# dynext_v0_2.net
KiCad netlist of a schematic drawn in EAGLE
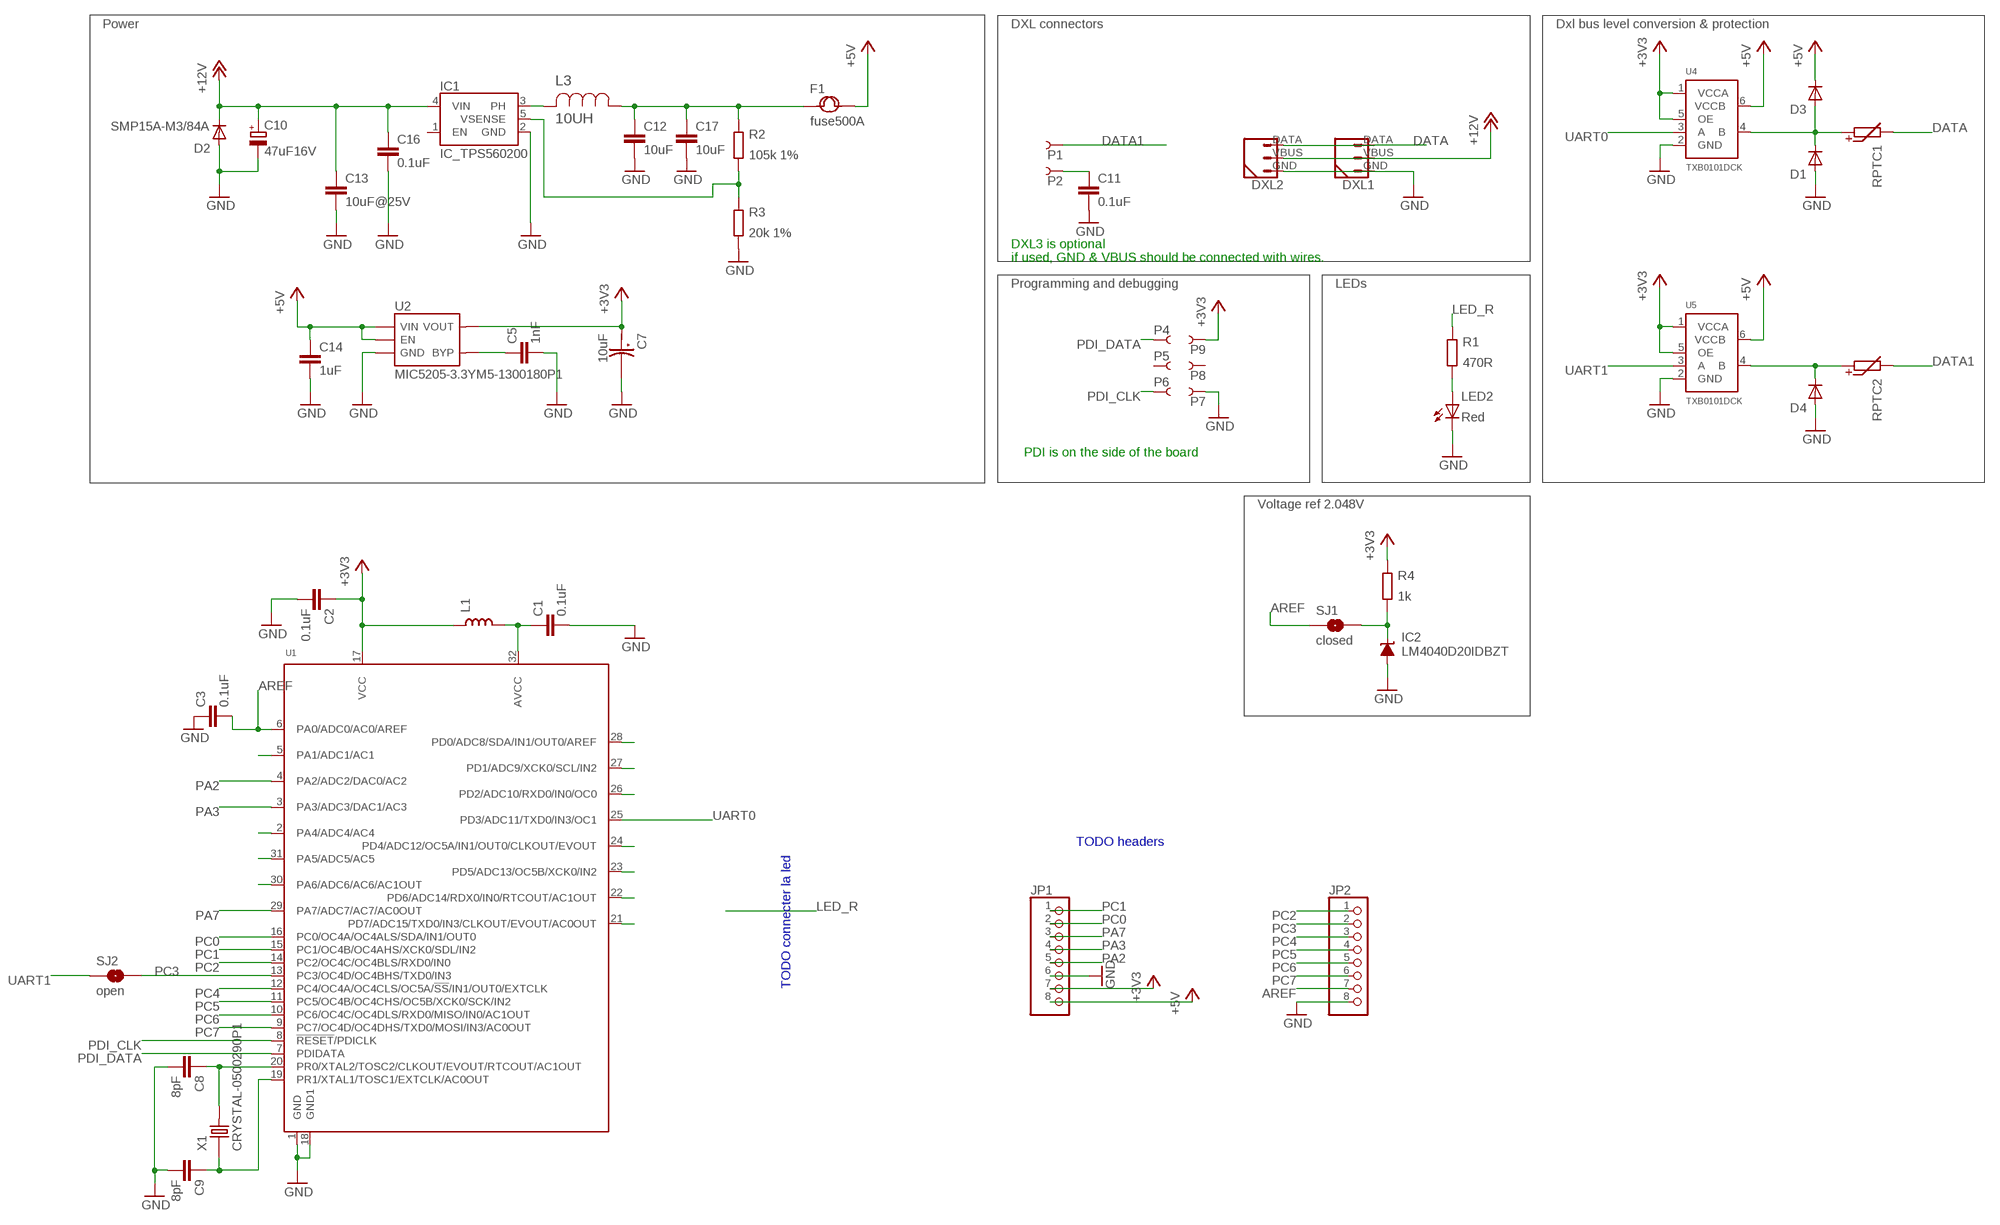
[diagram p0: schematic, sheet 1]

(export (version "E")
  (design (tool "Eeschema 10.0.6"))
  (components
    (comp (ref "C1")
      (value "0.1uF")
      (footprint "eagle-import:0402_N")
      (libsource (lib "eagle-import") (part "C0402"))
    )
    (comp (ref "C2")
      (value "0.1uF")
      (footprint "eagle-import:0402_N")
      (libsource (lib "eagle-import") (part "C0402"))
    )
    (comp (ref "C3")
      (value "0.1uF")
      (footprint "eagle-import:0402_N")
      (libsource (lib "eagle-import") (part "C0402"))
    )
    (comp (ref "C5")
      (value "1nF")
      (footprint "eagle-import:0402_N")
      (libsource (lib "eagle-import") (part "C0402"))
    )
    (comp (ref "C7")
      (value "10uF")
      (footprint "eagle-import:AVX-A")
      (libsource (lib "eagle-import") (part "C-POLAR-A"))
    )
    (comp (ref "C8")
      (value "8pF")
      (footprint "eagle-import:0402_N")
      (libsource (lib "eagle-import") (part "C0402"))
    )
    (comp (ref "C9")
      (value "8pF")
      (footprint "eagle-import:0402_N")
      (libsource (lib "eagle-import") (part "C0402"))
    )
    (comp (ref "C10")
      (value "47uF16V")
      (footprint "eagle-import:UD-5X5,8_NICHICON")
      (libsource (lib "eagle-import") (part "CPOL-EUUD-5X5,8"))
    )
    (comp (ref "C11")
      (value "0.1uF")
      (footprint "eagle-import:0402_N")
      (libsource (lib "eagle-import") (part "C0402"))
    )
    (comp (ref "C12")
      (value "10uF")
      (footprint "eagle-import:0805_N")
      (libsource (lib "eagle-import") (part "C0805"))
    )
    (comp (ref "C13")
      (value "10uF@25V")
      (footprint "eagle-import:0805_N")
      (libsource (lib "eagle-import") (part "C0805"))
    )
    (comp (ref "C14")
      (value "1uF")
      (footprint "eagle-import:0402_N")
      (libsource (lib "eagle-import") (part "C0402"))
    )
    (comp (ref "C16")
      (value "0.1uF")
      (footprint "eagle-import:0402_N")
      (libsource (lib "eagle-import") (part "C0402"))
    )
    (comp (ref "C17")
      (value "10uF")
      (footprint "eagle-import:0805_N")
      (libsource (lib "eagle-import") (part "C0805"))
    )
    (comp (ref "D1")
      (value "DIODE-SOD523")
      (footprint "eagle-import:SOD-523_N")
      (libsource (lib "eagle-import") (part "DIODE-SOD523"))
    )
    (comp (ref "D2")
      (value "SMP15A-M3/84A")
      (footprint "eagle-import:DO-220AA")
      (libsource (lib "eagle-import") (part "DIODE-SMP"))
    )
    (comp (ref "D3")
      (value "DIODE-SOD523")
      (footprint "eagle-import:SOD-523_N")
      (libsource (lib "eagle-import") (part "DIODE-SOD523"))
    )
    (comp (ref "D4")
      (value "DIODE-SOD523")
      (footprint "eagle-import:SOD-523_N")
      (libsource (lib "eagle-import") (part "DIODE-SOD523"))
    )
    (comp (ref "DXL1")
      (value "DYNAMIXEL_3POS-T")
      (footprint "eagle-import:DYNAMIXEL_3POS_TOP")
      (libsource (lib "eagle-import") (part "DYNAMIXEL_3POS-T"))
    )
    (comp (ref "DXL2")
      (value "DYNAMIXEL_3POS-T")
      (footprint "eagle-import:DYNAMIXEL_3POS_TOP")
      (libsource (lib "eagle-import") (part "DYNAMIXEL_3POS-T"))
    )
    (comp (ref "F1")
      (value "fuse500A")
      (footprint "eagle-import:F1206")
      (libsource (lib "eagle-import") (part "FUSE-1206"))
    )
    (comp (ref "IC1")
      (value "IC_TPS560200")
      (footprint "eagle-import:SOT-23-5_N")
      (libsource (lib "eagle-import") (part "IC_TPS560200"))
    )
    (comp (ref "IC2")
      (value "LM4040D20IDBZT")
      (footprint "eagle-import:DBZ_R-PDSO-G3")
      (fields (field (name "MPN") "LM4041A12IDBZR"))
      (libsource (lib "eagle-import") (part "LM4041DBZA12"))
    )
    (comp (ref "JP1")
      (value "PINHD-1X8R")
      (footprint "eagle-import:1X08_ROUND")
      (libsource (lib "eagle-import") (part "PINHD-1X8R"))
    )
    (comp (ref "JP2")
      (value "PINHD-1X8R")
      (footprint "eagle-import:1X08_ROUND")
      (libsource (lib "eagle-import") (part "PINHD-1X8R"))
    )
    (comp (ref "L1")
      (value "L0603")
      (footprint "eagle-import:0603_N")
      (libsource (lib "eagle-import") (part "L0603"))
    )
    (comp (ref "L3")
      (value "10UH")
      (footprint "eagle-import:IND_ELL4XG")
      (fields (field (name "MPN") "ELL4LG100MA"))
      (libsource (lib "eagle-import") (part "ELL-4XG4LG100MA"))
    )
    (comp (ref "LED2")
      (value "Red")
      (footprint "eagle-import:D_0603_N")
      (libsource (lib "eagle-import") (part "LED0603"))
    )
    (comp (ref "P1")
      (value "PIN_SMD_2X2.5")
      (footprint "eagle-import:PIN_SMD_2X2.5")
      (libsource (lib "eagle-import") (part "PIN_SMD_2X2.5"))
    )
    (comp (ref "P2")
      (value "PIN_SMD_2X2.5")
      (footprint "eagle-import:PIN_SMD_2X2.5")
      (libsource (lib "eagle-import") (part "PIN_SMD_2X2.5"))
    )
    (comp (ref "P4")
      (value "PIN_SMD_2X2.5")
      (footprint "eagle-import:PIN_SMD_2X2.5")
      (libsource (lib "eagle-import") (part "PIN_SMD_2X2.5"))
    )
    (comp (ref "P5")
      (value "PIN_SMD_1X1")
      (footprint "eagle-import:PIN_SMD_1X1")
      (libsource (lib "eagle-import") (part "PIN_SMD_1X1"))
    )
    (comp (ref "P6")
      (value "PIN_SMD_2X2.5")
      (footprint "eagle-import:PIN_SMD_2X2.5")
      (libsource (lib "eagle-import") (part "PIN_SMD_2X2.5"))
    )
    (comp (ref "P7")
      (value "PIN_SMD_2X2.5")
      (footprint "eagle-import:PIN_SMD_2X2.5")
      (libsource (lib "eagle-import") (part "PIN_SMD_2X2.5"))
    )
    (comp (ref "P8")
      (value "PIN_SMD_1X1")
      (footprint "eagle-import:PIN_SMD_1X1")
      (libsource (lib "eagle-import") (part "PIN_SMD_1X1"))
    )
    (comp (ref "P9")
      (value "PIN_SMD_2X2.5")
      (footprint "eagle-import:PIN_SMD_2X2.5")
      (libsource (lib "eagle-import") (part "PIN_SMD_2X2.5"))
    )
    (comp (ref "R1")
      (value "470R")
      (footprint "eagle-import:0402_N")
      (libsource (lib "eagle-import") (part "R0402"))
    )
    (comp (ref "R2")
      (value "105k 1%")
      (footprint "eagle-import:0402_N")
      (libsource (lib "eagle-import") (part "R0402"))
    )
    (comp (ref "R3")
      (value "20k 1%")
      (footprint "eagle-import:0402_N")
      (libsource (lib "eagle-import") (part "R0402"))
    )
    (comp (ref "R4")
      (value "1k")
      (footprint "eagle-import:0402_N")
      (libsource (lib "eagle-import") (part "R0402"))
    )
    (comp (ref "RPTC1")
      (value "R-PTC0603")
      (footprint "eagle-import:0603_N")
      (libsource (lib "eagle-import") (part "R-PTC0603"))
    )
    (comp (ref "RPTC2")
      (value "R-PTC0603")
      (footprint "eagle-import:0603_N")
      (libsource (lib "eagle-import") (part "R-PTC0603"))
    )
    (comp (ref "SJ1")
      (value "closed")
      (footprint "eagle-import:SJ_2S-TRACE2")
      (libsource (lib "eagle-import") (part "SOLDERJUMPER2_TRACE2"))
    )
    (comp (ref "SJ2")
      (value "open")
      (footprint "eagle-import:SJ_2S-NO")
      (libsource (lib "eagle-import") (part "SOLDERJUMPER2NO"))
    )
    (comp (ref "U1")
      (value "ATXMEGAE5-MU_MOD")
      (footprint "eagle-import:QFN-32_50P_L_MOD")
      (libsource (lib "eagle-import") (part "ATXMEGAE5-MU_MOD"))
    )
    (comp (ref "U2")
      (value "MIC5205-3.3YM5-1300180P1")
      (footprint "eagle-import:SOT23-5")
      (libsource (lib "eagle-import") (part "MIC5205-3.3YM5-1300180P1"))
    )
    (comp (ref "U4")
      (value "TXB0101DCK")
      (footprint "eagle-import:SC70-6")
      (libsource (lib "eagle-import") (part "TXB0101DCK"))
    )
    (comp (ref "U5")
      (value "TXB0101DCK")
      (footprint "eagle-import:SC70-6")
      (libsource (lib "eagle-import") (part "TXB0101DCK"))
    )
    (comp (ref "X1")
      (value "CRYSTAL-0500290P1")
      (footprint "eagle-import:2P-SMD-5.0X3.2")
      (libsource (lib "eagle-import") (part "CRYSTAL-0500290P1"))
    )
  )
  (nets
    (net (code "1") (name "+3V3") (class "Default")
      (node (ref "C2") (pin "1") (pinfunction "1_1") (pintype "passive"))
      (node (ref "C7") (pin "+") (pinfunction "1_+") (pintype "bidirectional"))
      (node (ref "JP1") (pin "7") (pinfunction "7_7") (pintype "passive"))
      (node (ref "L1") (pin "1") (pinfunction "1_1") (pintype "passive"))
      (node (ref "P9") (pin "PIN") (pinfunction "1_PIN") (pintype "bidirectional"))
      (node (ref "R4") (pin "2") (pinfunction "2_2") (pintype "passive"))
      (node (ref "U1") (pin "17") (pinfunction "VCC_17") (pintype "bidirectional"))
      (node (ref "U2") (pin "5") (pinfunction "VOUT_5") (pintype "bidirectional"))
      (node (ref "U4") (pin "1") (pinfunction "VCCA_1") (pintype "bidirectional"))
      (node (ref "U4") (pin "5") (pinfunction "OE_5") (pintype "bidirectional"))
      (node (ref "U5") (pin "1") (pinfunction "VCCA_1") (pintype "bidirectional"))
      (node (ref "U5") (pin "5") (pinfunction "OE_5") (pintype "bidirectional"))
    )
    (net (code "2") (name "+5V") (class "Default")
      (node (ref "C14") (pin "1") (pinfunction "1_1") (pintype "passive"))
      (node (ref "D3") (pin "C") (pinfunction "C_C") (pintype "passive"))
      (node (ref "F1") (pin "2") (pinfunction "2_2") (pintype "bidirectional"))
      (node (ref "JP1") (pin "8") (pinfunction "8_8") (pintype "passive"))
      (node (ref "U2") (pin "1") (pinfunction "VIN_1") (pintype "bidirectional"))
      (node (ref "U2") (pin "3") (pinfunction "EN_3") (pintype "bidirectional"))
      (node (ref "U4") (pin "6") (pinfunction "VCCB_6") (pintype "bidirectional"))
      (node (ref "U5") (pin "6") (pinfunction "VCCB_6") (pintype "bidirectional"))
    )
    (net (code "3") (name "+12V") (class "Default")
      (node (ref "C10") (pin "+") (pinfunction "+_+") (pintype "passive"))
      (node (ref "C13") (pin "1") (pinfunction "1_1") (pintype "passive"))
      (node (ref "C16") (pin "1") (pinfunction "1_1") (pintype "passive"))
      (node (ref "D2") (pin "C") (pinfunction "C_C") (pintype "passive"))
      (node (ref "DXL1") (pin "VBUS") (pinfunction "2_VBUS") (pintype "bidirectional"))
      (node (ref "DXL2") (pin "VBUS") (pinfunction "2_VBUS") (pintype "bidirectional"))
      (node (ref "IC1") (pin "4") (pinfunction "VIN_4") (pintype "bidirectional"))
    )
    (net (code "4") (name "/AREF") (class "Default")
      (node (ref "C3") (pin "2") (pinfunction "2_2") (pintype "passive"))
      (node (ref "JP2") (pin "7") (pinfunction "7_7") (pintype "passive"))
      (node (ref "SJ1") (pin "1") (pinfunction "1_1") (pintype "passive"))
      (node (ref "U1") (pin "6") (pinfunction "PA0/ADC0/AC0/AREF_6") (pintype "bidirectional"))
    )
    (net (code "5") (name "/DATA") (class "Default")
      (node (ref "DXL1") (pin "DATA") (pinfunction "3_DATA") (pintype "bidirectional"))
      (node (ref "DXL2") (pin "DATA") (pinfunction "3_DATA") (pintype "bidirectional"))
      (node (ref "RPTC1") (pin "2") (pinfunction "2_2") (pintype "passive"))
    )
    (net (code "6") (name "/DATA1") (class "Default")
      (node (ref "P1") (pin "PIN") (pinfunction "1_PIN") (pintype "bidirectional"))
      (node (ref "RPTC2") (pin "2") (pinfunction "2_2") (pintype "passive"))
    )
    (net (code "7") (name "/LED_R") (class "Default")
      (node (ref "R1") (pin "2") (pinfunction "2_2") (pintype "passive"))
    )
    (net (code "8") (name "/PA2") (class "Default")
      (node (ref "JP1") (pin "5") (pinfunction "5_5") (pintype "passive"))
      (node (ref "U1") (pin "4") (pinfunction "PA2/ADC2/DAC0/AC2_4") (pintype "bidirectional"))
    )
    (net (code "9") (name "/PA3") (class "Default")
      (node (ref "JP1") (pin "4") (pinfunction "4_4") (pintype "passive"))
      (node (ref "U1") (pin "3") (pinfunction "PA3/ADC3/DAC1/AC3_3") (pintype "bidirectional"))
    )
    (net (code "10") (name "/PA7") (class "Default")
      (node (ref "JP1") (pin "3") (pinfunction "3_3") (pintype "passive"))
      (node (ref "U1") (pin "29") (pinfunction "PA7/ADC7/AC7/AC0OUT_29") (pintype "bidirectional"))
    )
    (net (code "11") (name "/PC0") (class "Default")
      (node (ref "JP1") (pin "2") (pinfunction "2_2") (pintype "passive"))
      (node (ref "U1") (pin "16") (pinfunction "PC0/OC4A/OC4ALS/SDA/IN1/OUT0_16") (pintype "bidirectional"))
    )
    (net (code "12") (name "/PC1") (class "Default")
      (node (ref "JP1") (pin "1") (pinfunction "1_1") (pintype "passive"))
      (node (ref "U1") (pin "15") (pinfunction "PC1/OC4B/OC4AHS/XCK0/SDL/IN2_15") (pintype "bidirectional"))
    )
    (net (code "13") (name "/PC2") (class "Default")
      (node (ref "JP2") (pin "1") (pinfunction "1_1") (pintype "passive"))
      (node (ref "U1") (pin "14") (pinfunction "PC2/OC4C/OC4BLS/RXD0/IN0_14") (pintype "bidirectional"))
    )
    (net (code "14") (name "/PC3") (class "Default")
      (node (ref "JP2") (pin "2") (pinfunction "2_2") (pintype "passive"))
      (node (ref "SJ2") (pin "2") (pinfunction "2_2") (pintype "passive"))
      (node (ref "U1") (pin "13") (pinfunction "PC3/OC4D/OC4BHS/TXD0/IN3_13") (pintype "bidirectional"))
    )
    (net (code "15") (name "/PC4") (class "Default")
      (node (ref "JP2") (pin "3") (pinfunction "3_3") (pintype "passive"))
      (node (ref "U1") (pin "12") (pinfunction "PC4/OC4A/OC4CLS/OC5A/~{SS}/IN1/OUT0/EXTCLK_12") (pintype "bidirectional"))
    )
    (net (code "16") (name "/PC5") (class "Default")
      (node (ref "JP2") (pin "4") (pinfunction "4_4") (pintype "passive"))
      (node (ref "U1") (pin "11") (pinfunction "PC5/OC4B/OC4CHS/OC5B/XCK0/SCK/IN2_11") (pintype "bidirectional"))
    )
    (net (code "17") (name "/PC6") (class "Default")
      (node (ref "JP2") (pin "5") (pinfunction "5_5") (pintype "passive"))
      (node (ref "U1") (pin "10") (pinfunction "PC6/OC4C/OC4DLS/RXD0/MISO/IN0/AC1OUT_10") (pintype "bidirectional"))
    )
    (net (code "18") (name "/PC7") (class "Default")
      (node (ref "JP2") (pin "6") (pinfunction "6_6") (pintype "passive"))
      (node (ref "U1") (pin "9") (pinfunction "PC7/OC4D/OC4DHS/TXD0/MOSI/IN3/AC0OUT_9") (pintype "bidirectional"))
    )
    (net (code "19") (name "/PDI_CLK") (class "Default")
      (node (ref "P6") (pin "PIN") (pinfunction "1_PIN") (pintype "bidirectional"))
      (node (ref "U1") (pin "8") (pinfunction "~{RESET}/PDICLK_8") (pintype "bidirectional"))
    )
    (net (code "20") (name "/PDI_DATA") (class "Default")
      (node (ref "P4") (pin "PIN") (pinfunction "1_PIN") (pintype "bidirectional"))
      (node (ref "U1") (pin "7") (pinfunction "PDIDATA_7") (pintype "bidirectional"))
    )
    (net (code "21") (name "/UART0") (class "Default")
      (node (ref "U1") (pin "25") (pinfunction "PD3/ADC11/TXD0/IN3/OC1_25") (pintype "bidirectional"))
      (node (ref "U4") (pin "3") (pinfunction "A_3") (pintype "bidirectional"))
    )
    (net (code "22") (name "/UART1") (class "Default")
      (node (ref "SJ2") (pin "1") (pinfunction "1_1") (pintype "passive"))
      (node (ref "U5") (pin "3") (pinfunction "A_3") (pintype "bidirectional"))
    )
    (net (code "23") (name "GND") (class "Default")
      (node (ref "C1") (pin "2") (pinfunction "2_2") (pintype "passive"))
      (node (ref "C10") (pin "-") (pinfunction "-_-") (pintype "passive"))
      (node (ref "C11") (pin "2") (pinfunction "2_2") (pintype "passive"))
      (node (ref "C12") (pin "2") (pinfunction "2_2") (pintype "passive"))
      (node (ref "C13") (pin "2") (pinfunction "2_2") (pintype "passive"))
      (node (ref "C14") (pin "2") (pinfunction "2_2") (pintype "passive"))
      (node (ref "C16") (pin "2") (pinfunction "2_2") (pintype "passive"))
      (node (ref "C17") (pin "2") (pinfunction "2_2") (pintype "passive"))
      (node (ref "C2") (pin "2") (pinfunction "2_2") (pintype "passive"))
      (node (ref "C3") (pin "1") (pinfunction "1_1") (pintype "passive"))
      (node (ref "C5") (pin "2") (pinfunction "2_2") (pintype "passive"))
      (node (ref "C7") (pin "-") (pinfunction "2_-") (pintype "bidirectional"))
      (node (ref "C8") (pin "2") (pinfunction "2_2") (pintype "passive"))
      (node (ref "C9") (pin "2") (pinfunction "2_2") (pintype "passive"))
      (node (ref "D1") (pin "A") (pinfunction "A_A") (pintype "passive"))
      (node (ref "D2") (pin "A") (pinfunction "A_A") (pintype "passive"))
      (node (ref "D4") (pin "A") (pinfunction "A_A") (pintype "passive"))
      (node (ref "DXL1") (pin "GND") (pinfunction "1_GND") (pintype "bidirectional"))
      (node (ref "DXL2") (pin "GND") (pinfunction "1_GND") (pintype "bidirectional"))
      (node (ref "IC1") (pin "2") (pinfunction "GND_2") (pintype "input"))
      (node (ref "IC2") (pin "2") (pinfunction "A_2") (pintype "passive"))
      (node (ref "JP1") (pin "6") (pinfunction "6_6") (pintype "passive"))
      (node (ref "JP2") (pin "8") (pinfunction "8_8") (pintype "passive"))
      (node (ref "LED2") (pin "C") (pinfunction "C_C") (pintype "passive"))
      (node (ref "P7") (pin "PIN") (pinfunction "1_PIN") (pintype "bidirectional"))
      (node (ref "R3") (pin "1") (pinfunction "1_1") (pintype "passive"))
      (node (ref "U1") (pin "1") (pinfunction "GND_1") (pintype "bidirectional"))
      (node (ref "U1") (pin "18") (pinfunction "GND1_18") (pintype "bidirectional"))
      (node (ref "U2") (pin "2") (pinfunction "GND_2") (pintype "bidirectional"))
      (node (ref "U4") (pin "2") (pinfunction "GND_2") (pintype "bidirectional"))
      (node (ref "U5") (pin "2") (pinfunction "GND_2") (pintype "bidirectional"))
    )
    (net (code "24") (name "Net-(C12-Pad1)") (class "Default")
      (node (ref "C12") (pin "1") (pinfunction "1_1") (pintype "passive"))
      (node (ref "C17") (pin "1") (pinfunction "1_1") (pintype "passive"))
      (node (ref "F1") (pin "1") (pinfunction "1_1") (pintype "bidirectional"))
      (node (ref "L3") (pin "1") (pinfunction "1_1") (pintype "passive"))
      (node (ref "R2") (pin "2") (pinfunction "2_2") (pintype "passive"))
    )
    (net (code "25") (name "Net-(IC1-PH)") (class "Default")
      (node (ref "IC1") (pin "3") (pinfunction "PH_3") (pintype "bidirectional"))
      (node (ref "L3") (pin "2") (pinfunction "2_2") (pintype "passive"))
    )
    (net (code "26") (name "Net-(IC1-VSENSE)") (class "Default")
      (node (ref "IC1") (pin "5") (pinfunction "VSENSE_5") (pintype "bidirectional"))
      (node (ref "R2") (pin "1") (pinfunction "1_1") (pintype "passive"))
      (node (ref "R3") (pin "2") (pinfunction "2_2") (pintype "passive"))
    )
    (net (code "27") (name "Net-(IC2-C)") (class "Default")
      (node (ref "IC2") (pin "1") (pinfunction "C_1") (pintype "passive"))
      (node (ref "R4") (pin "1") (pinfunction "1_1") (pintype "passive"))
      (node (ref "SJ1") (pin "2") (pinfunction "2_2") (pintype "passive"))
    )
    (net (code "28") (name "Net-(LED2-PadA)") (class "Default")
      (node (ref "LED2") (pin "A") (pinfunction "A_A") (pintype "passive"))
      (node (ref "R1") (pin "1") (pinfunction "1_1") (pintype "passive"))
    )
    (net (code "29") (name "Net-(P2-1)") (class "Default")
      (node (ref "C11") (pin "1") (pinfunction "1_1") (pintype "passive"))
      (node (ref "P2") (pin "PIN") (pinfunction "1_PIN") (pintype "bidirectional"))
    )
    (net (code "30") (name "Net-(U1-AVCC)") (class "Default")
      (node (ref "C1") (pin "1") (pinfunction "1_1") (pintype "passive"))
      (node (ref "L1") (pin "2") (pinfunction "2_2") (pintype "passive"))
      (node (ref "U1") (pin "32") (pinfunction "AVCC_32") (pintype "bidirectional"))
    )
    (net (code "31") (name "Net-(U1-PR0{slash}XTAL2{slash}TOSC2{slash}CLKOUT{slash}EVOUT{slash}RTCOUT{slash}AC1OUT)") (class "Default")
      (node (ref "C8") (pin "1") (pinfunction "1_1") (pintype "passive"))
      (node (ref "U1") (pin "20") (pinfunction "PR0/XTAL2/TOSC2/CLKOUT/EVOUT/RTCOUT/AC1OUT_20") (pintype "bidirectional"))
      (node (ref "X1") (pin "2") (pinfunction "2_2") (pintype "passive"))
    )
    (net (code "32") (name "Net-(U1-PR1{slash}XTAL1{slash}TOSC1{slash}EXTCLK{slash}AC0OUT)") (class "Default")
      (node (ref "C9") (pin "1") (pinfunction "1_1") (pintype "passive"))
      (node (ref "U1") (pin "19") (pinfunction "PR1/XTAL1/TOSC1/EXTCLK/AC0OUT_19") (pintype "bidirectional"))
      (node (ref "X1") (pin "1") (pinfunction "1_1") (pintype "passive"))
    )
    (net (code "33") (name "Net-(U2-BYP)") (class "Default")
      (node (ref "C5") (pin "1") (pinfunction "1_1") (pintype "passive"))
      (node (ref "U2") (pin "4") (pinfunction "BYP_4") (pintype "bidirectional"))
    )
    (net (code "34") (name "Net-(U4-B)") (class "Default")
      (node (ref "D1") (pin "C") (pinfunction "C_C") (pintype "passive"))
      (node (ref "D3") (pin "A") (pinfunction "A_A") (pintype "passive"))
      (node (ref "RPTC1") (pin "1") (pinfunction "1_1") (pintype "passive"))
      (node (ref "U4") (pin "4") (pinfunction "B_4") (pintype "bidirectional"))
    )
    (net (code "35") (name "Net-(U5-B)") (class "Default")
      (node (ref "D4") (pin "C") (pinfunction "C_C") (pintype "passive"))
      (node (ref "RPTC2") (pin "1") (pinfunction "1_1") (pintype "passive"))
      (node (ref "U5") (pin "4") (pinfunction "B_4") (pintype "bidirectional"))
    )
    (net (code "36") (name "unconnected-(IC1-EN-Pad1)") (class "Default")
      (node (ref "IC1") (pin "1") (pinfunction "EN_1") (pintype "input"))
    )
    (net (code "37") (name "unconnected-(P5-1-PadP$1)") (class "Default")
      (node (ref "P5") (pin "P$1") (pinfunction "1_P$1") (pintype "bidirectional"))
    )
    (net (code "38") (name "unconnected-(P8-1-PadP$1)") (class "Default")
      (node (ref "P8") (pin "P$1") (pinfunction "1_P$1") (pintype "bidirectional"))
    )
    (net (code "39") (name "unconnected-(U1-PA1{slash}ADC1{slash}AC1-Pad5)") (class "Default")
      (node (ref "U1") (pin "5") (pinfunction "PA1/ADC1/AC1_5") (pintype "bidirectional"))
    )
    (net (code "40") (name "unconnected-(U1-PA4{slash}ADC4{slash}AC4-Pad2)") (class "Default")
      (node (ref "U1") (pin "2") (pinfunction "PA4/ADC4/AC4_2") (pintype "bidirectional"))
    )
    (net (code "41") (name "unconnected-(U1-PA5{slash}ADC5{slash}AC5-Pad31)") (class "Default")
      (node (ref "U1") (pin "31") (pinfunction "PA5/ADC5/AC5_31") (pintype "bidirectional"))
    )
    (net (code "42") (name "unconnected-(U1-PA6{slash}ADC6{slash}AC6{slash}AC1OUT-Pad30)") (class "Default")
      (node (ref "U1") (pin "30") (pinfunction "PA6/ADC6/AC6/AC1OUT_30") (pintype "bidirectional"))
    )
    (net (code "43") (name "unconnected-(U1-PD0{slash}ADC8{slash}SDA{slash}IN1{slash}OUT0{slash}AREF-Pad28)") (class "Default")
      (node (ref "U1") (pin "28") (pinfunction "PD0/ADC8/SDA/IN1/OUT0/AREF_28") (pintype "bidirectional"))
    )
    (net (code "44") (name "unconnected-(U1-PD1{slash}ADC9{slash}XCK0{slash}SCL{slash}IN2-Pad27)") (class "Default")
      (node (ref "U1") (pin "27") (pinfunction "PD1/ADC9/XCK0/SCL/IN2_27") (pintype "bidirectional"))
    )
    (net (code "45") (name "unconnected-(U1-PD2{slash}ADC10{slash}RXD0{slash}IN0{slash}OC0-Pad26)") (class "Default")
      (node (ref "U1") (pin "26") (pinfunction "PD2/ADC10/RXD0/IN0/OC0_26") (pintype "bidirectional"))
    )
    (net (code "46") (name "unconnected-(U1-PD4{slash}ADC12{slash}OC5A{slash}IN1{slash}OUT0{slash}CLKOUT{slash}EVOUT-Pad24)") (class "Default")
      (node (ref "U1") (pin "24") (pinfunction "PD4/ADC12/OC5A/IN1/OUT0/CLKOUT/EVOUT_24") (pintype "bidirectional"))
    )
    (net (code "47") (name "unconnected-(U1-PD5{slash}ADC13{slash}OC5B{slash}XCK0{slash}IN2-Pad23)") (class "Default")
      (node (ref "U1") (pin "23") (pinfunction "PD5/ADC13/OC5B/XCK0/IN2_23") (pintype "bidirectional"))
    )
    (net (code "48") (name "unconnected-(U1-PD6{slash}ADC14{slash}RDX0{slash}IN0{slash}RTCOUT{slash}AC1OUT-Pad22)") (class "Default")
      (node (ref "U1") (pin "22") (pinfunction "PD6/ADC14/RDX0/IN0/RTCOUT/AC1OUT_22") (pintype "bidirectional"))
    )
    (net (code "49") (name "unconnected-(U1-PD7{slash}ADC15{slash}TXD0{slash}IN3{slash}CLKOUT{slash}EVOUT{slash}AC0OUT-Pad21)") (class "Default")
      (node (ref "U1") (pin "21") (pinfunction "PD7/ADC15/TXD0/IN3/CLKOUT/EVOUT/AC0OUT_21") (pintype "bidirectional"))
    )
  )
)
